# amelia_B_v1.net
KiCad netlist of a schematic drawn in EAGLE
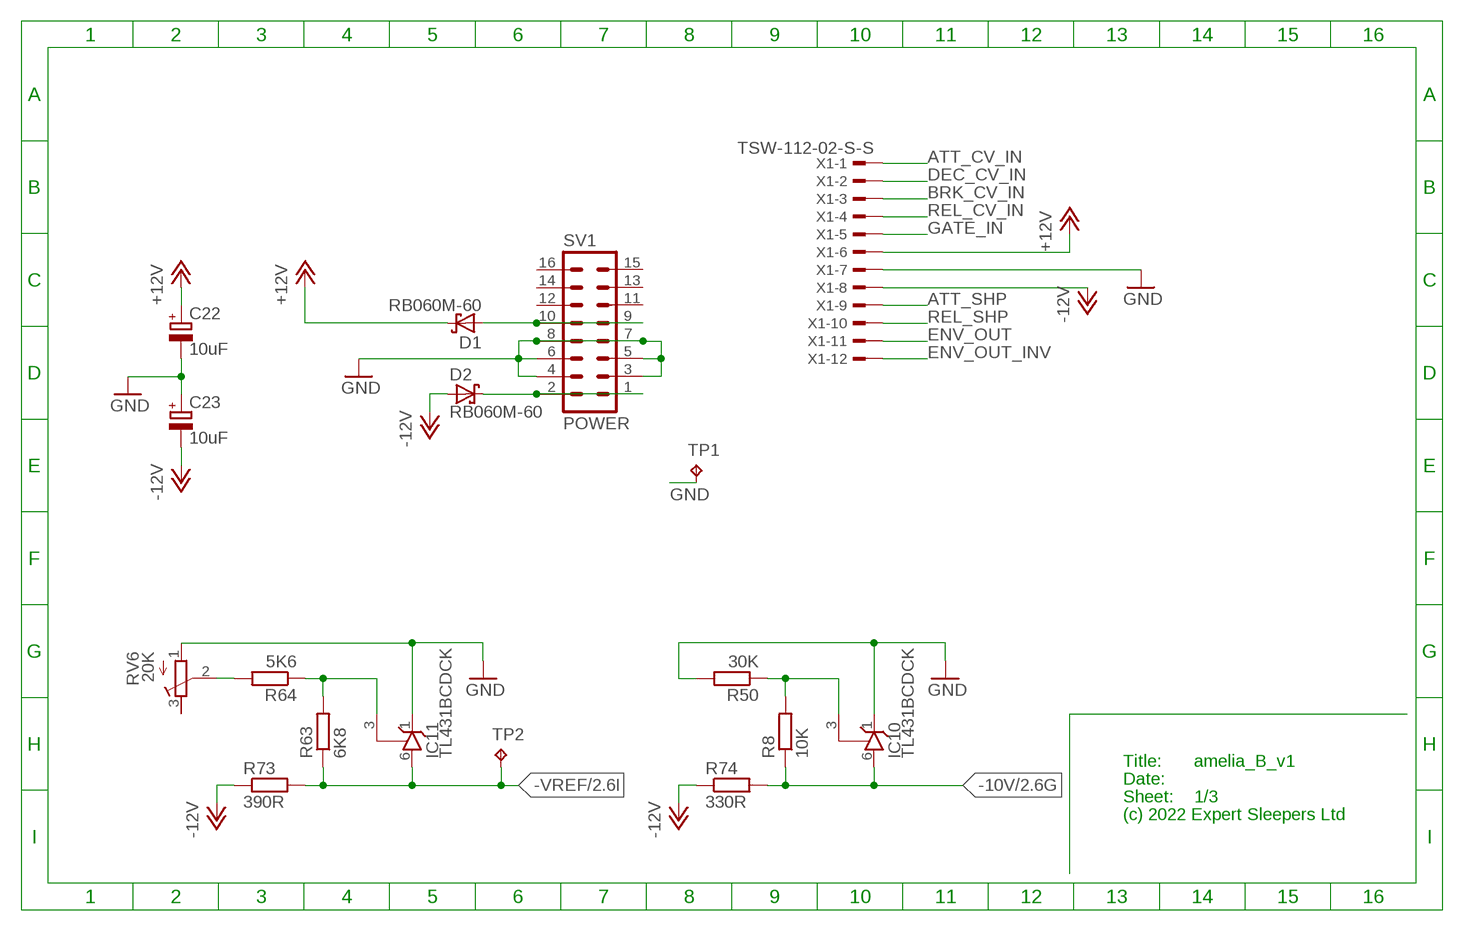
[diagram p0: schematic, sheet 1]
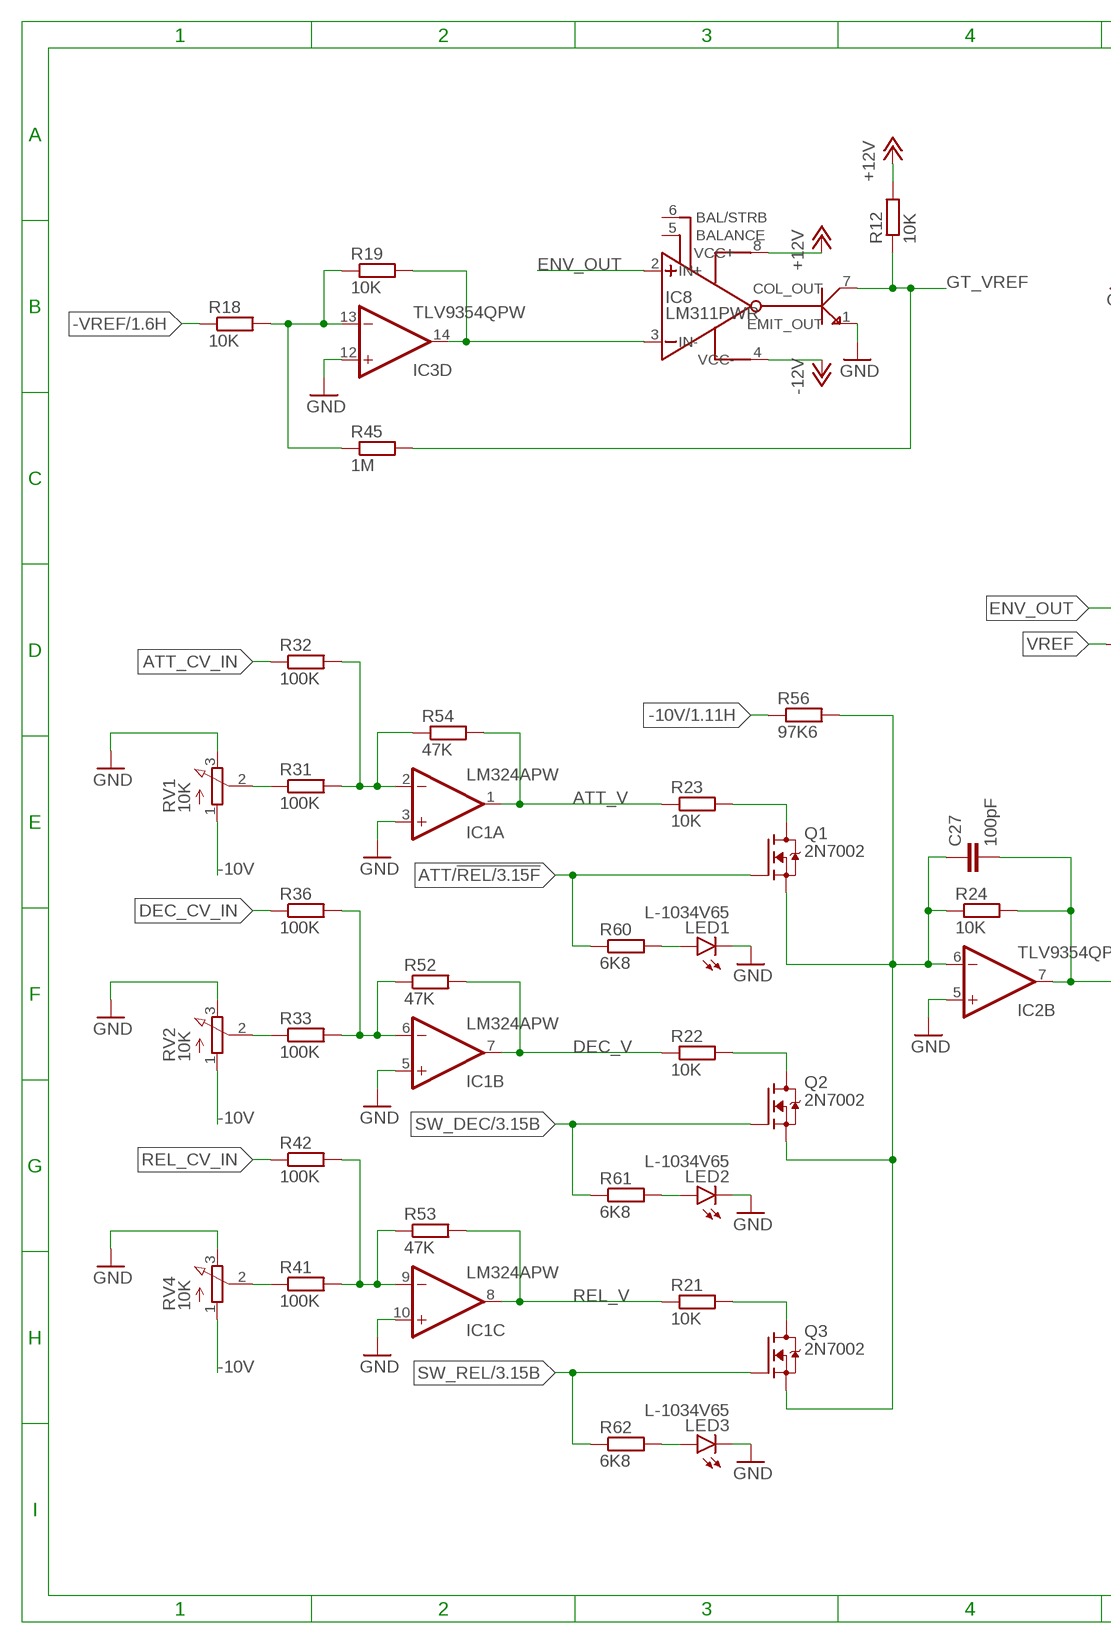
[diagram p1: schematic, sheet 2, part 1 of 2]
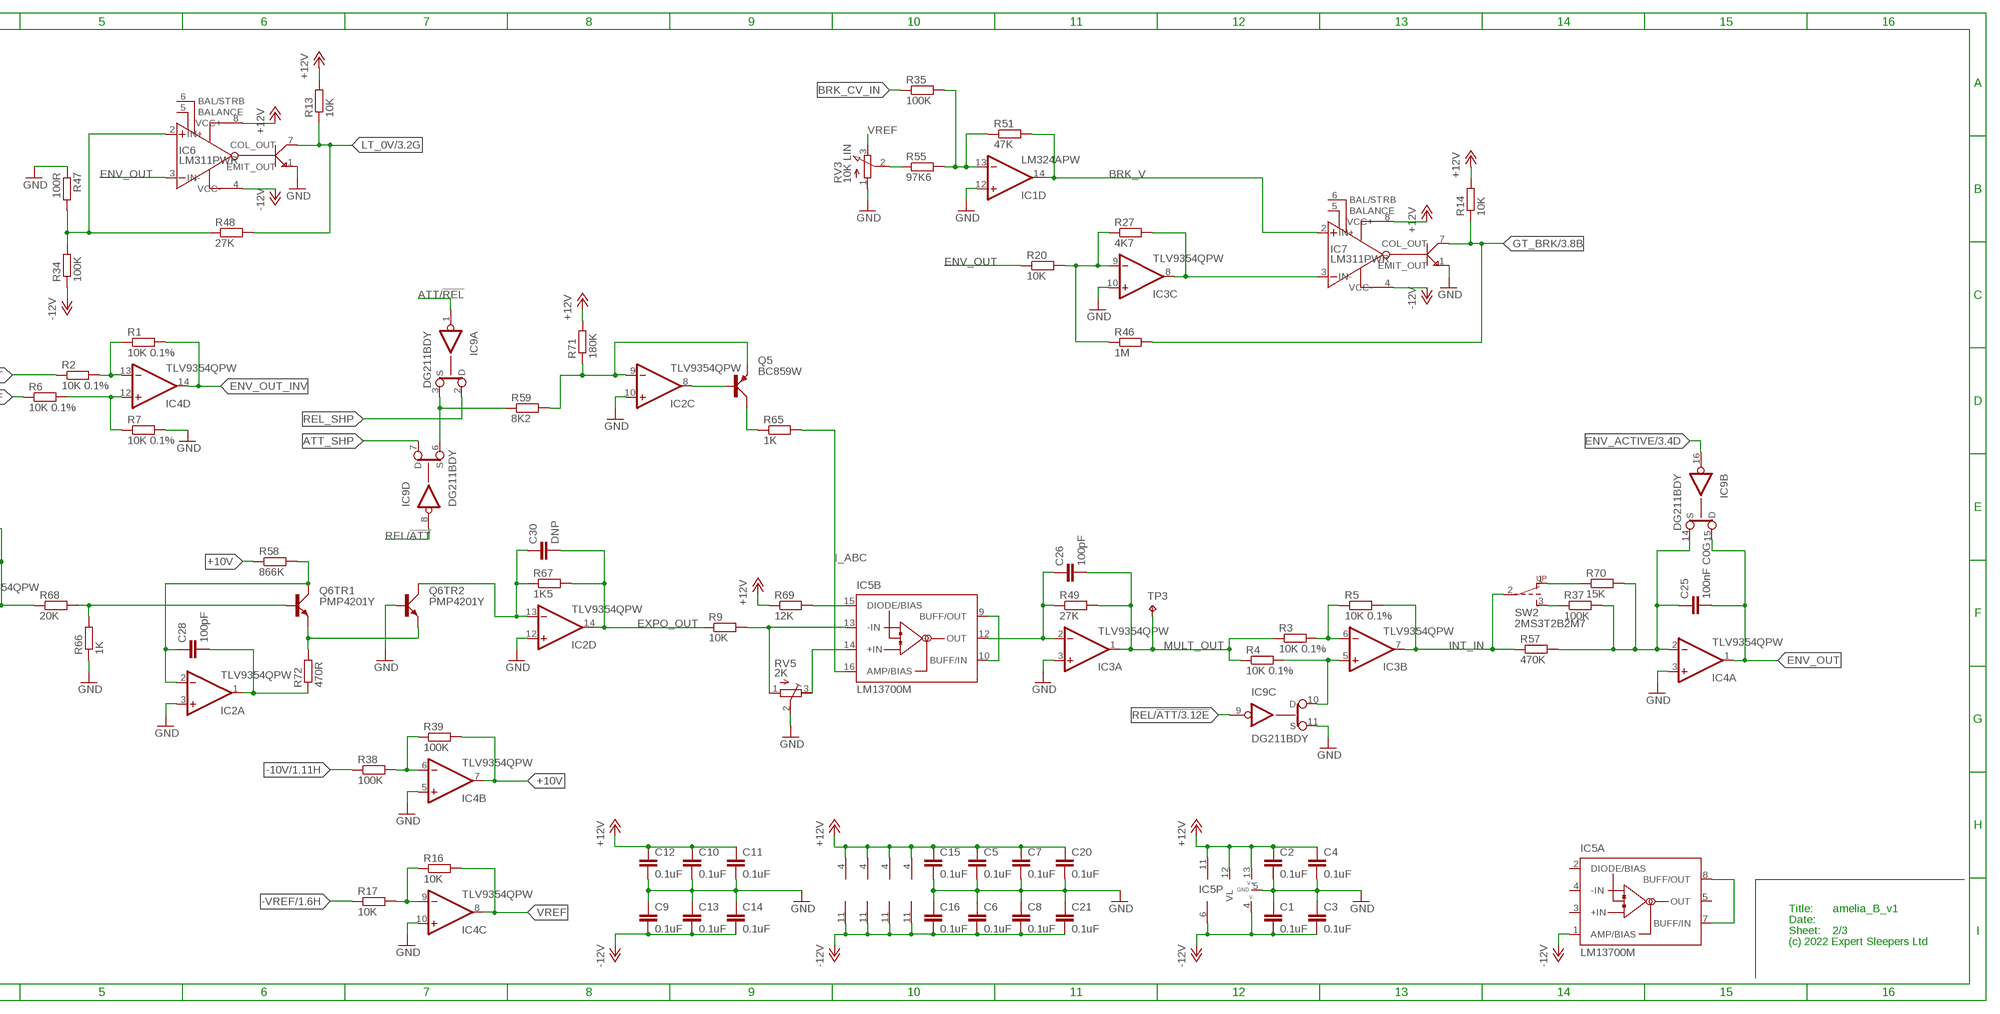
[diagram p2: schematic, sheet 2, part 2 of 2]
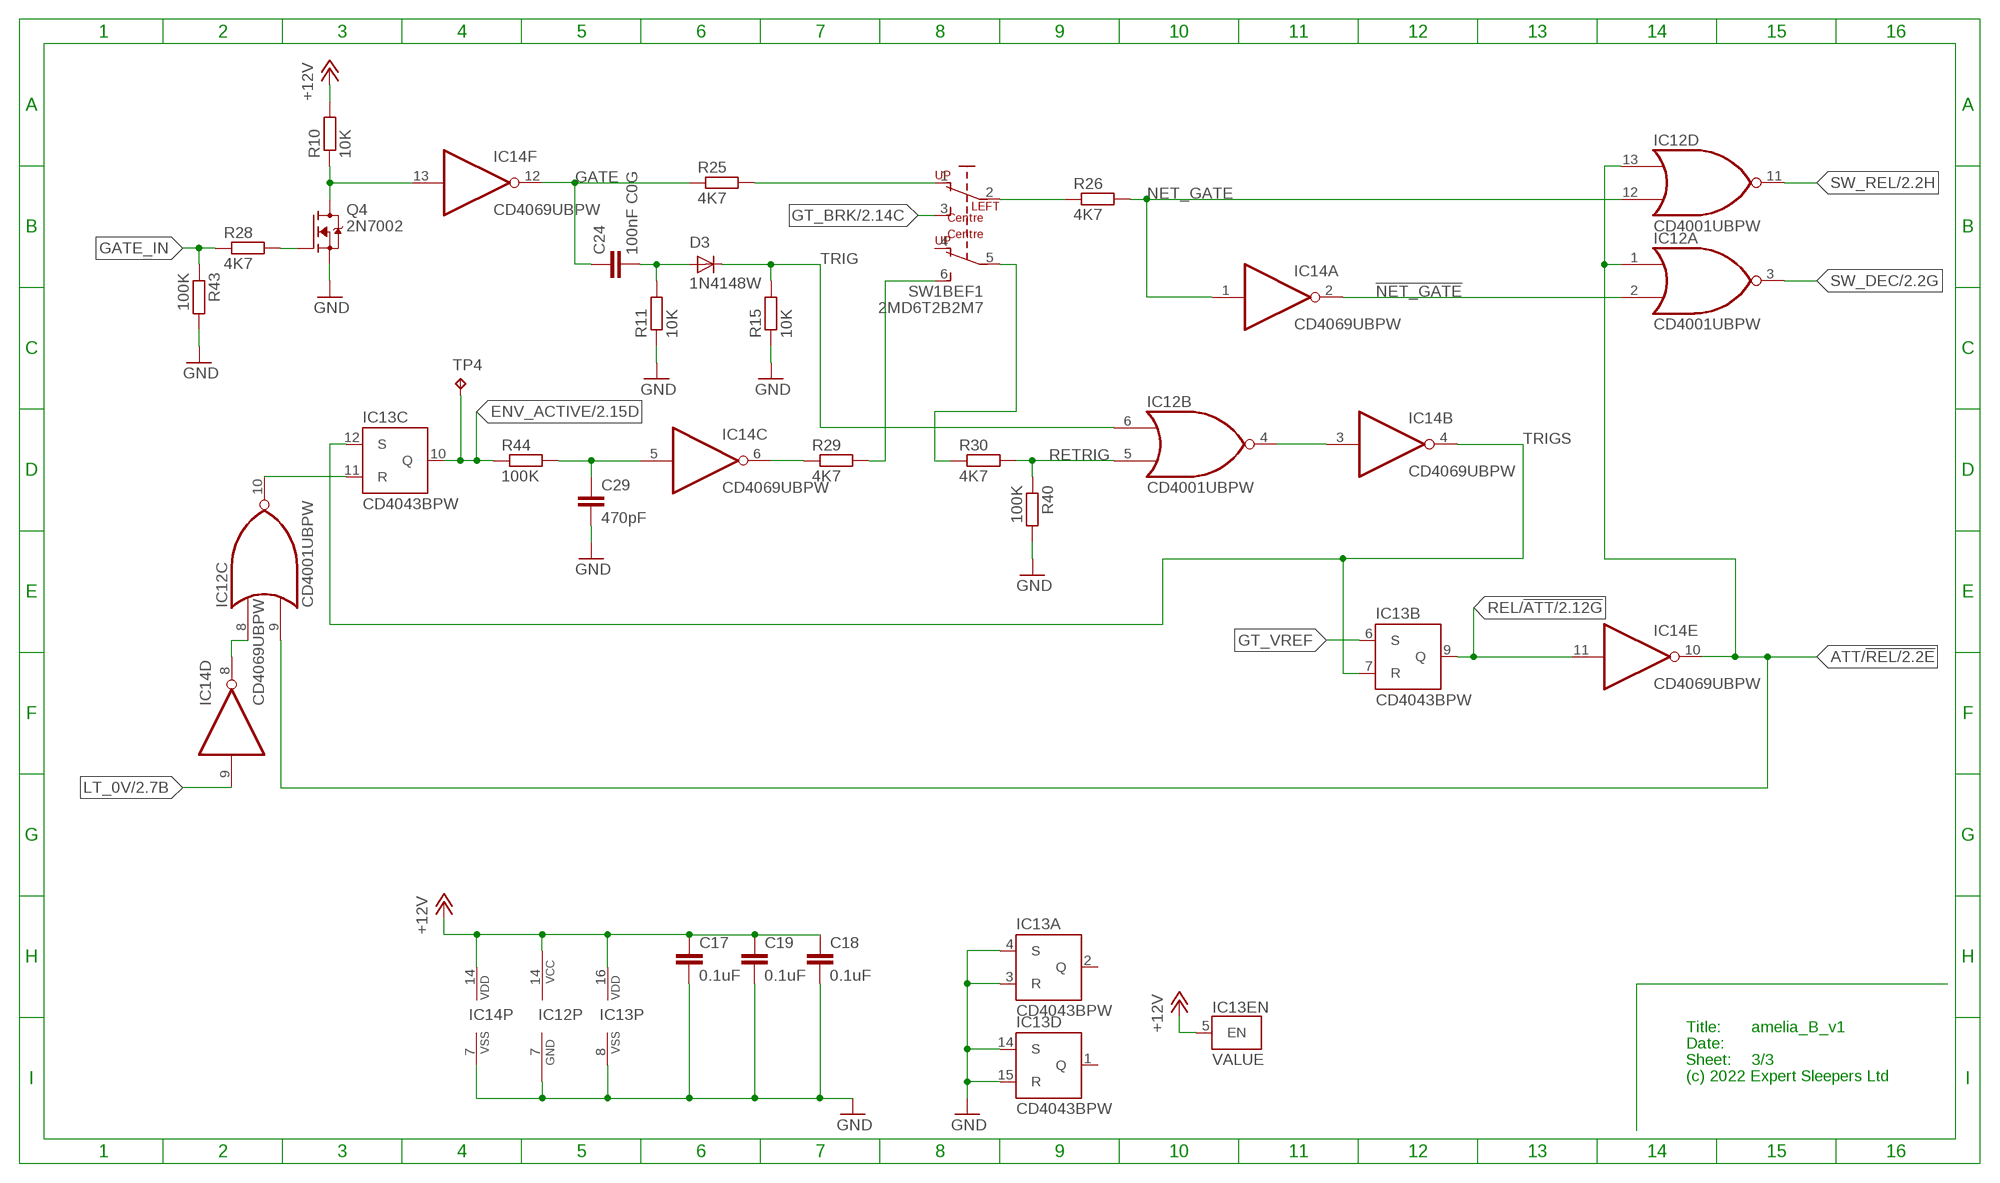
[diagram p3: schematic, sheet 3]

(export (version "E")
  (design (tool "Eeschema 10.0.6"))
  (components
    (comp (ref "C22")
      (value "10uF")
      (footprint "eagle-import:UD-4X5,8_NICHICON")
      (libsource (lib "eagle-import") (part "CPOL-EUUD-4X5,8"))
    )
    (comp (ref "C23")
      (value "10uF")
      (footprint "eagle-import:UD-4X5,8_NICHICON")
      (libsource (lib "eagle-import") (part "CPOL-EUUD-4X5,8"))
    )
    (comp (ref "D1")
      (value "RB060M-60")
      (footprint "eagle-import:SOD123FL")
      (libsource (lib "eagle-import") (part "RB060M-60"))
    )
    (comp (ref "D2")
      (value "RB060M-60")
      (footprint "eagle-import:SOD123FL")
      (libsource (lib "eagle-import") (part "RB060M-60"))
    )
    (comp (ref "IC10")
      (value "TL431BCDCK")
      (footprint "eagle-import:DCK_SC-70")
      (libsource (lib "eagle-import") (part "TL431DCKBC"))
    )
    (comp (ref "IC11")
      (value "TL431BCDCK")
      (footprint "eagle-import:DCK_SC-70")
      (libsource (lib "eagle-import") (part "TL431DCKBC"))
    )
    (comp (ref "R8")
      (value "10K")
      (footprint "eagle-import:R0603")
      (libsource (lib "eagle-import") (part "R-EU_R0603"))
    )
    (comp (ref "R50")
      (value "30K")
      (footprint "eagle-import:R0603")
      (libsource (lib "eagle-import") (part "R-EU_R0603"))
    )
    (comp (ref "R63")
      (value "6K8")
      (footprint "eagle-import:R0603")
      (libsource (lib "eagle-import") (part "R-EU_R0603"))
    )
    (comp (ref "R64")
      (value "5K6")
      (footprint "eagle-import:R0603")
      (libsource (lib "eagle-import") (part "R-EU_R0603"))
    )
    (comp (ref "R73")
      (value "390R")
      (footprint "eagle-import:R1206")
      (libsource (lib "eagle-import") (part "R-EU_R1206"))
    )
    (comp (ref "R74")
      (value "330R")
      (footprint "eagle-import:R1206")
      (libsource (lib "eagle-import") (part "R-EU_R1206"))
    )
    (comp (ref "RV6")
      (value "20K")
      (footprint "eagle-import:TC33X")
      (libsource (lib "eagle-import") (part "TC33X"))
    )
    (comp (ref "SV1")
      (value "POWER")
      (footprint "eagle-import:ML16")
      (libsource (lib "eagle-import") (part "ML16"))
    )
    (comp (ref "TP1")
      (value "RA2")
      (footprint "eagle-import:P1-13")
      (libsource (lib "eagle-import") (part "TPPAD1-13"))
    )
    (comp (ref "TP2")
      (value "RA2")
      (footprint "eagle-import:P1-13")
      (libsource (lib "eagle-import") (part "TPPAD1-13"))
    )
    (comp (ref "X1")
      (value "TSW-112-02-S-S")
      (footprint "eagle-import:TSW-112-02-S-S")
      (libsource (lib "eagle-import") (part "TSW-112-02-S-S"))
    )
    (comp (ref "C1")
      (value "0.1uF")
      (footprint "eagle-import:C0402")
      (libsource (lib "eagle-import") (part "C-EUC0402"))
    )
    (comp (ref "C2")
      (value "0.1uF")
      (footprint "eagle-import:C0402")
      (libsource (lib "eagle-import") (part "C-EUC0402"))
    )
    (comp (ref "C3")
      (value "0.1uF")
      (footprint "eagle-import:C0402")
      (libsource (lib "eagle-import") (part "C-EUC0402"))
    )
    (comp (ref "C4")
      (value "0.1uF")
      (footprint "eagle-import:C0402")
      (libsource (lib "eagle-import") (part "C-EUC0402"))
    )
    (comp (ref "C5")
      (value "0.1uF")
      (footprint "eagle-import:C0402")
      (libsource (lib "eagle-import") (part "C-EUC0402"))
    )
    (comp (ref "C6")
      (value "0.1uF")
      (footprint "eagle-import:C0402")
      (libsource (lib "eagle-import") (part "C-EUC0402"))
    )
    (comp (ref "C7")
      (value "0.1uF")
      (footprint "eagle-import:C0402")
      (libsource (lib "eagle-import") (part "C-EUC0402"))
    )
    (comp (ref "C8")
      (value "0.1uF")
      (footprint "eagle-import:C0402")
      (libsource (lib "eagle-import") (part "C-EUC0402"))
    )
    (comp (ref "C9")
      (value "0.1uF")
      (footprint "eagle-import:C0402")
      (libsource (lib "eagle-import") (part "C-EUC0402"))
    )
    (comp (ref "C10")
      (value "0.1uF")
      (footprint "eagle-import:C0402")
      (libsource (lib "eagle-import") (part "C-EUC0402"))
    )
    (comp (ref "C11")
      (value "0.1uF")
      (footprint "eagle-import:C0402")
      (libsource (lib "eagle-import") (part "C-EUC0402"))
    )
    (comp (ref "C12")
      (value "0.1uF")
      (footprint "eagle-import:C0402")
      (libsource (lib "eagle-import") (part "C-EUC0402"))
    )
    (comp (ref "C13")
      (value "0.1uF")
      (footprint "eagle-import:C0402")
      (libsource (lib "eagle-import") (part "C-EUC0402"))
    )
    (comp (ref "C14")
      (value "0.1uF")
      (footprint "eagle-import:C0402")
      (libsource (lib "eagle-import") (part "C-EUC0402"))
    )
    (comp (ref "C15")
      (value "0.1uF")
      (footprint "eagle-import:C0402")
      (libsource (lib "eagle-import") (part "C-EUC0402"))
    )
    (comp (ref "C16")
      (value "0.1uF")
      (footprint "eagle-import:C0402")
      (libsource (lib "eagle-import") (part "C-EUC0402"))
    )
    (comp (ref "C20")
      (value "0.1uF")
      (footprint "eagle-import:C0402")
      (libsource (lib "eagle-import") (part "C-EUC0402"))
    )
    (comp (ref "C21")
      (value "0.1uF")
      (footprint "eagle-import:C0402")
      (libsource (lib "eagle-import") (part "C-EUC0402"))
    )
    (comp (ref "C25")
      (value "100nF C0G")
      (footprint "eagle-import:C1206")
      (libsource (lib "eagle-import") (part "C-EUC1206"))
    )
    (comp (ref "C26")
      (value "100pF")
      (footprint "eagle-import:C0603")
      (libsource (lib "eagle-import") (part "C-EUC0603"))
    )
    (comp (ref "C27")
      (value "100pF")
      (footprint "eagle-import:C0603")
      (libsource (lib "eagle-import") (part "C-EUC0603"))
    )
    (comp (ref "C28")
      (value "100pF")
      (footprint "eagle-import:C0603")
      (libsource (lib "eagle-import") (part "C-EUC0603"))
    )
    (comp (ref "C30")
      (value "DNP")
      (footprint "eagle-import:C0603")
      (libsource (lib "eagle-import") (part "C-EUC0603"))
    )
    (comp (ref "IC1")
      (value "LM324APW")
      (footprint "eagle-import:PW_R-PDSO-G14")
      (libsource (lib "eagle-import") (part "TL074PW"))
    )
    (comp (ref "IC2")
      (value "TLV9354QPW")
      (footprint "eagle-import:PW_R-PDSO-G14")
      (libsource (lib "eagle-import") (part "TL074PW"))
    )
    (comp (ref "IC3")
      (value "TLV9354QPW")
      (footprint "eagle-import:PW_R-PDSO-G14")
      (libsource (lib "eagle-import") (part "TL074PW"))
    )
    (comp (ref "IC4")
      (value "TLV9354QPW")
      (footprint "eagle-import:PW_R-PDSO-G14")
      (libsource (lib "eagle-import") (part "TL074PW"))
    )
    (comp (ref "IC5")
      (value "LM13700M")
      (footprint "eagle-import:SO16")
      (libsource (lib "eagle-import") (part "LM13700M"))
    )
    (comp (ref "IC6")
      (value "LM311PWR")
      (footprint "eagle-import:SOP65P640X120-8N")
      (fields (field (name "MOUSER_PART_NUMBER") "595-LM311PWR"))
      (libsource (lib "eagle-import") (part "LM311PWR"))
    )
    (comp (ref "IC7")
      (value "LM311PWR")
      (footprint "eagle-import:SOP65P640X120-8N")
      (fields (field (name "MOUSER_PART_NUMBER") "595-LM311PWR"))
      (libsource (lib "eagle-import") (part "LM311PWR"))
    )
    (comp (ref "IC8")
      (value "LM311PWR")
      (footprint "eagle-import:SOP65P640X120-8N")
      (fields (field (name "MOUSER_PART_NUMBER") "595-LM311PWR"))
      (libsource (lib "eagle-import") (part "LM311PWR"))
    )
    (comp (ref "IC9")
      (value "DG211BDY")
      (footprint "eagle-import:SO16")
      (libsource (lib "eagle-import") (part "DG211CJD"))
    )
    (comp (ref "LED1")
      (value "L-1034V65")
      (footprint "eagle-import:L-1034_V6.5MM")
      (libsource (lib "eagle-import") (part "L-1034V65"))
    )
    (comp (ref "LED2")
      (value "L-1034V65")
      (footprint "eagle-import:L-1034_V6.5MM")
      (libsource (lib "eagle-import") (part "L-1034V65"))
    )
    (comp (ref "LED3")
      (value "L-1034V65")
      (footprint "eagle-import:L-1034_V6.5MM")
      (libsource (lib "eagle-import") (part "L-1034V65"))
    )
    (comp (ref "Q1")
      (value "2N7002")
      (footprint "eagle-import:SOT23")
      (libsource (lib "eagle-import") (part "2N7002"))
    )
    (comp (ref "Q2")
      (value "2N7002")
      (footprint "eagle-import:SOT23")
      (libsource (lib "eagle-import") (part "2N7002"))
    )
    (comp (ref "Q3")
      (value "2N7002")
      (footprint "eagle-import:SOT23")
      (libsource (lib "eagle-import") (part "2N7002"))
    )
    (comp (ref "Q5")
      (value "BC859W")
      (footprint "eagle-import:SOT323")
      (libsource (lib "eagle-import") (part "BC859W"))
    )
    (comp (ref "Q6")
      (value "PMP4201Y")
      (footprint "eagle-import:SOT65P210X110-6N")
      (fields
        (field (name "ARROW_PART_NUMBER") "PMP4201Y,135")
        (field (name "MOUSER_PART_NUMBER") "771-PMP4201Y135")
      )
      (libsource (lib "eagle-import") (part "PMP4201Y"))
    )
    (comp (ref "R1")
      (value "10K 0.1%")
      (footprint "eagle-import:R0603")
      (libsource (lib "eagle-import") (part "R-EU_R0603"))
    )
    (comp (ref "R2")
      (value "10K 0.1%")
      (footprint "eagle-import:R0603")
      (libsource (lib "eagle-import") (part "R-EU_R0603"))
    )
    (comp (ref "R3")
      (value "10K 0.1%")
      (footprint "eagle-import:R0603")
      (libsource (lib "eagle-import") (part "R-EU_R0603"))
    )
    (comp (ref "R4")
      (value "10K 0.1%")
      (footprint "eagle-import:R0603")
      (libsource (lib "eagle-import") (part "R-EU_R0603"))
    )
    (comp (ref "R5")
      (value "10K 0.1%")
      (footprint "eagle-import:R0603")
      (libsource (lib "eagle-import") (part "R-EU_R0603"))
    )
    (comp (ref "R6")
      (value "10K 0.1%")
      (footprint "eagle-import:R0603")
      (libsource (lib "eagle-import") (part "R-EU_R0603"))
    )
    (comp (ref "R7")
      (value "10K 0.1%")
      (footprint "eagle-import:R0603")
      (libsource (lib "eagle-import") (part "R-EU_R0603"))
    )
    (comp (ref "R9")
      (value "10K")
      (footprint "eagle-import:R0603")
      (libsource (lib "eagle-import") (part "R-EU_R0603"))
    )
    (comp (ref "R12")
      (value "10K")
      (footprint "eagle-import:R0603")
      (libsource (lib "eagle-import") (part "R-EU_R0603"))
    )
    (comp (ref "R13")
      (value "10K")
      (footprint "eagle-import:R0603")
      (libsource (lib "eagle-import") (part "R-EU_R0603"))
    )
    (comp (ref "R14")
      (value "10K")
      (footprint "eagle-import:R0603")
      (libsource (lib "eagle-import") (part "R-EU_R0603"))
    )
    (comp (ref "R16")
      (value "10K")
      (footprint "eagle-import:R0603")
      (libsource (lib "eagle-import") (part "R-EU_R0603"))
    )
    (comp (ref "R17")
      (value "10K")
      (footprint "eagle-import:R0603")
      (libsource (lib "eagle-import") (part "R-EU_R0603"))
    )
    (comp (ref "R18")
      (value "10K")
      (footprint "eagle-import:R0603")
      (libsource (lib "eagle-import") (part "R-EU_R0603"))
    )
    (comp (ref "R19")
      (value "10K")
      (footprint "eagle-import:R0603")
      (libsource (lib "eagle-import") (part "R-EU_R0603"))
    )
    (comp (ref "R20")
      (value "10K")
      (footprint "eagle-import:R0603")
      (libsource (lib "eagle-import") (part "R-EU_R0603"))
    )
    (comp (ref "R21")
      (value "10K")
      (footprint "eagle-import:R0603")
      (libsource (lib "eagle-import") (part "R-EU_R0603"))
    )
    (comp (ref "R22")
      (value "10K")
      (footprint "eagle-import:R0603")
      (libsource (lib "eagle-import") (part "R-EU_R0603"))
    )
    (comp (ref "R23")
      (value "10K")
      (footprint "eagle-import:R0603")
      (libsource (lib "eagle-import") (part "R-EU_R0603"))
    )
    (comp (ref "R24")
      (value "10K")
      (footprint "eagle-import:R0603")
      (libsource (lib "eagle-import") (part "R-EU_R0603"))
    )
    (comp (ref "R27")
      (value "4K7")
      (footprint "eagle-import:R0603")
      (libsource (lib "eagle-import") (part "R-EU_R0603"))
    )
    (comp (ref "R31")
      (value "100K")
      (footprint "eagle-import:R0603")
      (libsource (lib "eagle-import") (part "R-EU_R0603"))
    )
    (comp (ref "R32")
      (value "100K")
      (footprint "eagle-import:R0603")
      (libsource (lib "eagle-import") (part "R-EU_R0603"))
    )
    (comp (ref "R33")
      (value "100K")
      (footprint "eagle-import:R0603")
      (libsource (lib "eagle-import") (part "R-EU_R0603"))
    )
    (comp (ref "R34")
      (value "100K")
      (footprint "eagle-import:R0603")
      (libsource (lib "eagle-import") (part "R-EU_R0603"))
    )
    (comp (ref "R35")
      (value "100K")
      (footprint "eagle-import:R0603")
      (libsource (lib "eagle-import") (part "R-EU_R0603"))
    )
    (comp (ref "R36")
      (value "100K")
      (footprint "eagle-import:R0603")
      (libsource (lib "eagle-import") (part "R-EU_R0603"))
    )
    (comp (ref "R37")
      (value "100K")
      (footprint "eagle-import:R0603")
      (libsource (lib "eagle-import") (part "R-EU_R0603"))
    )
    (comp (ref "R38")
      (value "100K")
      (footprint "eagle-import:R0603")
      (libsource (lib "eagle-import") (part "R-EU_R0603"))
    )
    (comp (ref "R39")
      (value "100K")
      (footprint "eagle-import:R0603")
      (libsource (lib "eagle-import") (part "R-EU_R0603"))
    )
    (comp (ref "R41")
      (value "100K")
      (footprint "eagle-import:R0603")
      (libsource (lib "eagle-import") (part "R-EU_R0603"))
    )
    (comp (ref "R42")
      (value "100K")
      (footprint "eagle-import:R0603")
      (libsource (lib "eagle-import") (part "R-EU_R0603"))
    )
    (comp (ref "R45")
      (value "1M")
      (footprint "eagle-import:R0603")
      (libsource (lib "eagle-import") (part "R-EU_R0603"))
    )
    (comp (ref "R46")
      (value "1M")
      (footprint "eagle-import:R0603")
      (libsource (lib "eagle-import") (part "R-EU_R0603"))
    )
    (comp (ref "R47")
      (value "100R")
      (footprint "eagle-import:R0603")
      (libsource (lib "eagle-import") (part "R-EU_R0603"))
    )
    (comp (ref "R48")
      (value "27K")
      (footprint "eagle-import:R0603")
      (libsource (lib "eagle-import") (part "R-EU_R0603"))
    )
    (comp (ref "R49")
      (value "27K")
      (footprint "eagle-import:R0603")
      (libsource (lib "eagle-import") (part "R-EU_R0603"))
    )
    (comp (ref "R51")
      (value "47K")
      (footprint "eagle-import:R0603")
      (libsource (lib "eagle-import") (part "R-EU_R0603"))
    )
    (comp (ref "R52")
      (value "47K")
      (footprint "eagle-import:R0603")
      (libsource (lib "eagle-import") (part "R-EU_R0603"))
    )
    (comp (ref "R53")
      (value "47K")
      (footprint "eagle-import:R0603")
      (libsource (lib "eagle-import") (part "R-EU_R0603"))
    )
    (comp (ref "R54")
      (value "47K")
      (footprint "eagle-import:R0603")
      (libsource (lib "eagle-import") (part "R-EU_R0603"))
    )
    (comp (ref "R55")
      (value "97K6")
      (footprint "eagle-import:R0603")
      (libsource (lib "eagle-import") (part "R-EU_R0603"))
    )
    (comp (ref "R56")
      (value "97K6")
      (footprint "eagle-import:R0603")
      (libsource (lib "eagle-import") (part "R-EU_R0603"))
    )
    (comp (ref "R57")
      (value "470K")
      (footprint "eagle-import:R0603")
      (libsource (lib "eagle-import") (part "R-EU_R0603"))
    )
    (comp (ref "R58")
      (value "866K")
      (footprint "eagle-import:R0603")
      (libsource (lib "eagle-import") (part "R-EU_R0603"))
    )
    (comp (ref "R59")
      (value "8K2")
      (footprint "eagle-import:R0603")
      (libsource (lib "eagle-import") (part "R-EU_R0603"))
    )
    (comp (ref "R60")
      (value "6K8")
      (footprint "eagle-import:R0603")
      (libsource (lib "eagle-import") (part "R-EU_R0603"))
    )
    (comp (ref "R61")
      (value "6K8")
      (footprint "eagle-import:R0603")
      (libsource (lib "eagle-import") (part "R-EU_R0603"))
    )
    (comp (ref "R62")
      (value "6K8")
      (footprint "eagle-import:R0603")
      (libsource (lib "eagle-import") (part "R-EU_R0603"))
    )
    (comp (ref "R65")
      (value "1K")
      (footprint "eagle-import:R0603")
      (libsource (lib "eagle-import") (part "R-EU_R0603"))
    )
    (comp (ref "R66")
      (value "1K")
      (footprint "eagle-import:R0603")
      (libsource (lib "eagle-import") (part "R-EU_R0603"))
    )
    (comp (ref "R67")
      (value "1K5")
      (footprint "eagle-import:R0603")
      (libsource (lib "eagle-import") (part "R-EU_R0603"))
    )
    (comp (ref "R68")
      (value "20K")
      (footprint "eagle-import:R0603")
      (libsource (lib "eagle-import") (part "R-EU_R0603"))
    )
    (comp (ref "R69")
      (value "12K")
      (footprint "eagle-import:R0603")
      (libsource (lib "eagle-import") (part "R-EU_R0603"))
    )
    (comp (ref "R70")
      (value "15K")
      (footprint "eagle-import:R0603")
      (libsource (lib "eagle-import") (part "R-EU_R0603"))
    )
    (comp (ref "R71")
      (value "180K")
      (footprint "eagle-import:R0603")
      (libsource (lib "eagle-import") (part "R-EU_R0603"))
    )
    (comp (ref "R72")
      (value "470R")
      (footprint "eagle-import:R0603")
      (libsource (lib "eagle-import") (part "R-EU_R0603"))
    )
    (comp (ref "RV1")
      (value "10K")
      (footprint "eagle-import:RD1610NOA0X")
      (libsource (lib "eagle-import") (part "RD1610NOA0X"))
    )
    (comp (ref "RV2")
      (value "10K")
      (footprint "eagle-import:RD1610NOA0X")
      (libsource (lib "eagle-import") (part "RD1610NOA0X"))
    )
    (comp (ref "RV3")
      (value "10K LIN")
      (footprint "eagle-import:RD1610NOA0X")
      (libsource (lib "eagle-import") (part "RD1610NOA0X"))
    )
    (comp (ref "RV4")
      (value "10K")
      (footprint "eagle-import:RD1610NOA0X")
      (libsource (lib "eagle-import") (part "RD1610NOA0X"))
    )
    (comp (ref "RV5")
      (value "2K")
      (footprint "eagle-import:RTRIM3296W")
      (libsource (lib "eagle-import") (part "T93YA"))
    )
    (comp (ref "SW2")
      (value "2MS3T2B2M7")
      (footprint "eagle-import:2MS1T2B2M7RE")
      (libsource (lib "eagle-import") (part "2MS3M7T2B2"))
    )
    (comp (ref "TP3")
      (value "RA2")
      (footprint "eagle-import:P1-13")
      (libsource (lib "eagle-import") (part "TPPAD1-13"))
    )
    (comp (ref "C17")
      (value "0.1uF")
      (footprint "eagle-import:C0402")
      (libsource (lib "eagle-import") (part "C-EUC0402"))
    )
    (comp (ref "C18")
      (value "0.1uF")
      (footprint "eagle-import:C0402")
      (libsource (lib "eagle-import") (part "C-EUC0402"))
    )
    (comp (ref "C19")
      (value "0.1uF")
      (footprint "eagle-import:C0402")
      (libsource (lib "eagle-import") (part "C-EUC0402"))
    )
    (comp (ref "C24")
      (value "100nF C0G")
      (footprint "eagle-import:C1206")
      (libsource (lib "eagle-import") (part "C-EUC1206"))
    )
    (comp (ref "C29")
      (value "470pF")
      (footprint "eagle-import:C0603")
      (libsource (lib "eagle-import") (part "C-EUC0603"))
    )
    (comp (ref "D3")
      (value "1N4148W")
      (footprint "eagle-import:SOD123")
      (libsource (lib "eagle-import") (part "1N4148W"))
    )
    (comp (ref "IC12")
      (value "CD4001UBPW")
      (footprint "eagle-import:TSSOP14")
      (libsource (lib "eagle-import") (part "CD4001UBPW"))
    )
    (comp (ref "IC13")
      (value "CD4043BPW")
      (footprint "eagle-import:TSSOP16")
      (libsource (lib "eagle-import") (part "CD4043BPW"))
    )
    (comp (ref "IC14")
      (value "CD4069UBPW")
      (footprint "eagle-import:TSSOP14")
      (libsource (lib "eagle-import") (part "CD4069UBPW"))
    )
    (comp (ref "Q4")
      (value "2N7002")
      (footprint "eagle-import:SOT23")
      (libsource (lib "eagle-import") (part "2N7002"))
    )
    (comp (ref "R10")
      (value "10K")
      (footprint "eagle-import:R0603")
      (libsource (lib "eagle-import") (part "R-EU_R0603"))
    )
    (comp (ref "R11")
      (value "10K")
      (footprint "eagle-import:R0603")
      (libsource (lib "eagle-import") (part "R-EU_R0603"))
    )
    (comp (ref "R15")
      (value "10K")
      (footprint "eagle-import:R0603")
      (libsource (lib "eagle-import") (part "R-EU_R0603"))
    )
    (comp (ref "R25")
      (value "4K7")
      (footprint "eagle-import:R0603")
      (libsource (lib "eagle-import") (part "R-EU_R0603"))
    )
    (comp (ref "R26")
      (value "4K7")
      (footprint "eagle-import:R0603")
      (libsource (lib "eagle-import") (part "R-EU_R0603"))
    )
    (comp (ref "R28")
      (value "4K7")
      (footprint "eagle-import:R0603")
      (libsource (lib "eagle-import") (part "R-EU_R0603"))
    )
    (comp (ref "R29")
      (value "4K7")
      (footprint "eagle-import:R0603")
      (libsource (lib "eagle-import") (part "R-EU_R0603"))
    )
    (comp (ref "R30")
      (value "4K7")
      (footprint "eagle-import:R0603")
      (libsource (lib "eagle-import") (part "R-EU_R0603"))
    )
    (comp (ref "R40")
      (value "100K")
      (footprint "eagle-import:R0603")
      (libsource (lib "eagle-import") (part "R-EU_R0603"))
    )
    (comp (ref "R43")
      (value "100K")
      (footprint "eagle-import:R0603")
      (libsource (lib "eagle-import") (part "R-EU_R0603"))
    )
    (comp (ref "R44")
      (value "100K")
      (footprint "eagle-import:R0603")
      (libsource (lib "eagle-import") (part "R-EU_R0603"))
    )
    (comp (ref "SW1")
      (value "2MD6T2B2M7")
      (footprint "eagle-import:2MD1T2B2M7RE")
      (libsource (lib "eagle-import") (part "2MD6M7T2B2"))
    )
    (comp (ref "TP4")
      (value "RA2")
      (footprint "eagle-import:P1-13")
      (libsource (lib "eagle-import") (part "TPPAD1-13"))
    )
  )
  (nets
    (net (code "1") (name "+10V") (class "Default")
      (node (ref "IC4") (pin "7") (pinfunction "OUT_7") (pintype "output"))
      (node (ref "R39") (pin "2") (pinfunction "2_2") (pintype "passive"))
      (node (ref "R58") (pin "1") (pinfunction "1_1") (pintype "passive"))
    )
    (net (code "2") (name "+12V") (class "Default")
      (node (ref "C10") (pin "1") (pinfunction "1_1") (pintype "passive"))
      (node (ref "C11") (pin "1") (pinfunction "1_1") (pintype "passive"))
      (node (ref "C12") (pin "1") (pinfunction "1_1") (pintype "passive"))
      (node (ref "C15") (pin "1") (pinfunction "1_1") (pintype "passive"))
      (node (ref "C17") (pin "1") (pinfunction "1_1") (pintype "passive"))
      (node (ref "C18") (pin "1") (pinfunction "1_1") (pintype "passive"))
      (node (ref "C19") (pin "1") (pinfunction "1_1") (pintype "passive"))
      (node (ref "C2") (pin "1") (pinfunction "1_1") (pintype "passive"))
      (node (ref "C20") (pin "1") (pinfunction "1_1") (pintype "passive"))
      (node (ref "C22") (pin "+") (pinfunction "+_+") (pintype "passive"))
      (node (ref "C4") (pin "1") (pinfunction "1_1") (pintype "passive"))
      (node (ref "C5") (pin "1") (pinfunction "1_1") (pintype "passive"))
      (node (ref "C7") (pin "1") (pinfunction "1_1") (pintype "passive"))
      (node (ref "D1") (pin "C") (pinfunction "C_C") (pintype "passive"))
      (node (ref "IC1") (pin "4") (pinfunction "V+_4") (pintype "power_in"))
      (node (ref "IC12") (pin "14") (pinfunction "VCC_14") (pintype "power_in"))
      (node (ref "IC13") (pin "16") (pinfunction "VDD_16") (pintype "power_in"))
      (node (ref "IC13") (pin "5") (pinfunction "EN_5") (pintype "input"))
      (node (ref "IC14") (pin "14") (pinfunction "VDD_14") (pintype "power_in"))
      (node (ref "IC2") (pin "4") (pinfunction "V+_4") (pintype "power_in"))
      (node (ref "IC3") (pin "4") (pinfunction "V+_4") (pintype "power_in"))
      (node (ref "IC4") (pin "4") (pinfunction "V+_4") (pintype "power_in"))
      (node (ref "IC5") (pin "11") (pinfunction "V+_11") (pintype "power_in"))
      (node (ref "IC6") (pin "8") (pinfunction "VCC+_8") (pintype "power_in"))
      (node (ref "IC7") (pin "8") (pinfunction "VCC+_8") (pintype "power_in"))
      (node (ref "IC8") (pin "8") (pinfunction "VCC+_8") (pintype "power_in"))
      (node (ref "IC9") (pin "12") (pinfunction "VL_12") (pintype "input"))
      (node (ref "IC9") (pin "13") (pinfunction "V+_13") (pintype "power_in"))
      (node (ref "R10") (pin "2") (pinfunction "2_2") (pintype "passive"))
      (node (ref "R12") (pin "2") (pinfunction "2_2") (pintype "passive"))
      (node (ref "R13") (pin "2") (pinfunction "2_2") (pintype "passive"))
      (node (ref "R14") (pin "2") (pinfunction "2_2") (pintype "passive"))
      (node (ref "R69") (pin "1") (pinfunction "1_1") (pintype "passive"))
      (node (ref "R71") (pin "2") (pinfunction "2_2") (pintype "passive"))
      (node (ref "X1") (pin "6") (pinfunction "1_6") (pintype "passive"))
    )
    (net (code "3") (name "-10V") (class "Default")
      (node (ref "IC10") (pin "6") (pinfunction "A_6") (pintype "passive"))
      (node (ref "R38") (pin "1") (pinfunction "1_1") (pintype "passive"))
      (node (ref "R56") (pin "1") (pinfunction "1_1") (pintype "passive"))
      (node (ref "R74") (pin "2") (pinfunction "2_2") (pintype "passive"))
      (node (ref "R8") (pin "1") (pinfunction "1_1") (pintype "passive"))
      (node (ref "RV1") (pin "1") (pinfunction "A_1") (pintype "passive"))
      (node (ref "RV2") (pin "1") (pinfunction "A_1") (pintype "passive"))
      (node (ref "RV4") (pin "1") (pinfunction "A_1") (pintype "passive"))
    )
    (net (code "4") (name "-12V") (class "Default")
      (node (ref "C1") (pin "2") (pinfunction "2_2") (pintype "passive"))
      (node (ref "C13") (pin "2") (pinfunction "2_2") (pintype "passive"))
      (node (ref "C14") (pin "2") (pinfunction "2_2") (pintype "passive"))
      (node (ref "C16") (pin "2") (pinfunction "2_2") (pintype "passive"))
      (node (ref "C21") (pin "2") (pinfunction "2_2") (pintype "passive"))
      (node (ref "C23") (pin "-") (pinfunction "-_-") (pintype "passive"))
      (node (ref "C3") (pin "2") (pinfunction "2_2") (pintype "passive"))
      (node (ref "C6") (pin "2") (pinfunction "2_2") (pintype "passive"))
      (node (ref "C8") (pin "2") (pinfunction "2_2") (pintype "passive"))
      (node (ref "C9") (pin "2") (pinfunction "2_2") (pintype "passive"))
      (node (ref "D2") (pin "A") (pinfunction "A_A") (pintype "passive"))
      (node (ref "IC1") (pin "11") (pinfunction "V-_11") (pintype "power_in"))
      (node (ref "IC2") (pin "11") (pinfunction "V-_11") (pintype "power_in"))
      (node (ref "IC3") (pin "11") (pinfunction "V-_11") (pintype "power_in"))
      (node (ref "IC4") (pin "11") (pinfunction "V-_11") (pintype "power_in"))
      (node (ref "IC5") (pin "1") (pinfunction "AMP/BIAS_1") (pintype "passive"))
      (node (ref "IC5") (pin "6") (pinfunction "V-_6") (pintype "power_in"))
      (node (ref "IC6") (pin "4") (pinfunction "VCC-_4") (pintype "power_in"))
      (node (ref "IC7") (pin "4") (pinfunction "VCC-_4") (pintype "power_in"))
      (node (ref "IC8") (pin "4") (pinfunction "VCC-_4") (pintype "power_in"))
      (node (ref "IC9") (pin "4") (pinfunction "V-_4") (pintype "power_in"))
      (node (ref "R34") (pin "1") (pinfunction "1_1") (pintype "passive"))
      (node (ref "R73") (pin "1") (pinfunction "1_1") (pintype "passive"))
      (node (ref "R74") (pin "1") (pinfunction "1_1") (pintype "passive"))
      (node (ref "X1") (pin "8") (pinfunction "1_8") (pintype "passive"))
    )
    (net (code "5") (name "-VREF") (class "Default")
      (node (ref "IC11") (pin "6") (pinfunction "A_6") (pintype "passive"))
      (node (ref "R17") (pin "1") (pinfunction "1_1") (pintype "passive"))
      (node (ref "R18") (pin "1") (pinfunction "1_1") (pintype "passive"))
      (node (ref "R63") (pin "1") (pinfunction "1_1") (pintype "passive"))
      (node (ref "R73") (pin "2") (pinfunction "2_2") (pintype "passive"))
      (node (ref "TP2") (pin "TP") (pinfunction "TP_TP") (pintype "input"))
    )
    (net (code "6") (name "ATT_CV_IN") (class "Default")
      (node (ref "R32") (pin "1") (pinfunction "1_1") (pintype "passive"))
      (node (ref "X1") (pin "1") (pinfunction "1_1") (pintype "passive"))
    )
    (net (code "7") (name "ATT_SHP") (class "Default")
      (node (ref "IC9") (pin "7") (pinfunction "D_7") (pintype "bidirectional"))
      (node (ref "X1") (pin "9") (pinfunction "1_9") (pintype "passive"))
    )
    (net (code "8") (name "ATT_V") (class "Default")
      (node (ref "IC1") (pin "1") (pinfunction "OUT_1") (pintype "output"))
      (node (ref "R23") (pin "1") (pinfunction "1_1") (pintype "passive"))
      (node (ref "R54") (pin "2") (pinfunction "2_2") (pintype "passive"))
    )
    (net (code "9") (name "ATT{slash}~{REL}") (class "Default")
      (node (ref "IC12") (pin "1") (pinfunction "I0_1") (pintype "input"))
      (node (ref "IC12") (pin "13") (pinfunction "I0_13") (pintype "input"))
      (node (ref "IC12") (pin "9") (pinfunction "I1_9") (pintype "input"))
      (node (ref "IC14") (pin "10") (pinfunction "O_10") (pintype "output"))
      (node (ref "IC9") (pin "1") (pinfunction "IN_1") (pintype "input"))
      (node (ref "Q1") (pin "1") (pinfunction "G_1") (pintype "passive"))
      (node (ref "R60") (pin "1") (pinfunction "1_1") (pintype "passive"))
    )
    (net (code "10") (name "BRK_CV_IN") (class "Default")
      (node (ref "R35") (pin "1") (pinfunction "1_1") (pintype "passive"))
      (node (ref "X1") (pin "3") (pinfunction "1_3") (pintype "passive"))
    )
    (net (code "11") (name "BRK_V") (class "Default")
      (node (ref "IC1") (pin "14") (pinfunction "OUT_14") (pintype "output"))
      (node (ref "IC7") (pin "2") (pinfunction "IN+_2") (pintype "input"))
      (node (ref "R51") (pin "2") (pinfunction "2_2") (pintype "passive"))
    )
    (net (code "12") (name "DEC_CV_IN") (class "Default")
      (node (ref "R36") (pin "1") (pinfunction "1_1") (pintype "passive"))
      (node (ref "X1") (pin "2") (pinfunction "1_2") (pintype "passive"))
    )
    (net (code "13") (name "DEC_V") (class "Default")
      (node (ref "IC1") (pin "7") (pinfunction "OUT_7") (pintype "output"))
      (node (ref "R22") (pin "1") (pinfunction "1_1") (pintype "passive"))
      (node (ref "R52") (pin "2") (pinfunction "2_2") (pintype "passive"))
    )
    (net (code "14") (name "ENV_ACTIVE") (class "Default")
      (node (ref "IC13") (pin "10") (pinfunction "Q_10") (pintype "output"))
      (node (ref "IC9") (pin "16") (pinfunction "IN_16") (pintype "input"))
      (node (ref "R44") (pin "1") (pinfunction "1_1") (pintype "passive"))
      (node (ref "TP4") (pin "TP") (pinfunction "TP_TP") (pintype "input"))
    )
    (net (code "15") (name "ENV_OUT") (class "Default")
      (node (ref "C25") (pin "2") (pinfunction "2_2") (pintype "passive"))
      (node (ref "IC4") (pin "1") (pinfunction "OUT_1") (pintype "output"))
      (node (ref "IC6") (pin "3") (pinfunction "IN-_3") (pintype "input"))
      (node (ref "IC8") (pin "2") (pinfunction "IN+_2") (pintype "input"))
      (node (ref "IC9") (pin "15") (pinfunction "D_15") (pintype "bidirectional"))
      (node (ref "R2") (pin "1") (pinfunction "1_1") (pintype "passive"))
      (node (ref "R20") (pin "1") (pinfunction "1_1") (pintype "passive"))
      (node (ref "X1") (pin "11") (pinfunction "1_11") (pintype "passive"))
    )
    (net (code "16") (name "ENV_OUT_INV") (class "Default")
      (node (ref "IC4") (pin "14") (pinfunction "OUT_14") (pintype "output"))
      (node (ref "R1") (pin "2") (pinfunction "2_2") (pintype "passive"))
      (node (ref "X1") (pin "12") (pinfunction "1_12") (pintype "passive"))
    )
    (net (code "17") (name "EXPO_OUT") (class "Default")
      (node (ref "C30") (pin "2") (pinfunction "2_2") (pintype "passive"))
      (node (ref "IC2") (pin "14") (pinfunction "OUT_14") (pintype "output"))
      (node (ref "R67") (pin "2") (pinfunction "2_2") (pintype "passive"))
      (node (ref "R9") (pin "1") (pinfunction "1_1") (pintype "passive"))
    )
    (net (code "18") (name "GATE") (class "Default")
      (node (ref "C24") (pin "1") (pinfunction "1_1") (pintype "passive"))
      (node (ref "IC14") (pin "12") (pinfunction "O_12") (pintype "output"))
      (node (ref "R25") (pin "1") (pinfunction "1_1") (pintype "passive"))
    )
    (net (code "19") (name "GATE_IN") (class "Default")
      (node (ref "R28") (pin "1") (pinfunction "1_1") (pintype "passive"))
      (node (ref "R43") (pin "1") (pinfunction "1_1") (pintype "passive"))
      (node (ref "X1") (pin "5") (pinfunction "1_5") (pintype "passive"))
    )
    (net (code "20") (name "GND") (class "Default")
      (node (ref "C1") (pin "1") (pinfunction "1_1") (pintype "passive"))
      (node (ref "C10") (pin "2") (pinfunction "2_2") (pintype "passive"))
      (node (ref "C11") (pin "2") (pinfunction "2_2") (pintype "passive"))
      (node (ref "C12") (pin "2") (pinfunction "2_2") (pintype "passive"))
      (node (ref "C13") (pin "1") (pinfunction "1_1") (pintype "passive"))
      (node (ref "C14") (pin "1") (pinfunction "1_1") (pintype "passive"))
      (node (ref "C15") (pin "2") (pinfunction "2_2") (pintype "passive"))
      (node (ref "C16") (pin "1") (pinfunction "1_1") (pintype "passive"))
      (node (ref "C17") (pin "2") (pinfunction "2_2") (pintype "passive"))
      (node (ref "C18") (pin "2") (pinfunction "2_2") (pintype "passive"))
      (node (ref "C19") (pin "2") (pinfunction "2_2") (pintype "passive"))
      (node (ref "C2") (pin "2") (pinfunction "2_2") (pintype "passive"))
      (node (ref "C20") (pin "2") (pinfunction "2_2") (pintype "passive"))
      (node (ref "C21") (pin "1") (pinfunction "1_1") (pintype "passive"))
      (node (ref "C22") (pin "-") (pinfunction "-_-") (pintype "passive"))
      (node (ref "C23") (pin "+") (pinfunction "+_+") (pintype "passive"))
      (node (ref "C29") (pin "2") (pinfunction "2_2") (pintype "passive"))
      (node (ref "C3") (pin "1") (pinfunction "1_1") (pintype "passive"))
      (node (ref "C4") (pin "2") (pinfunction "2_2") (pintype "passive"))
      (node (ref "C5") (pin "2") (pinfunction "2_2") (pintype "passive"))
      (node (ref "C6") (pin "1") (pinfunction "1_1") (pintype "passive"))
      (node (ref "C7") (pin "2") (pinfunction "2_2") (pintype "passive"))
      (node (ref "C8") (pin "1") (pinfunction "1_1") (pintype "passive"))
      (node (ref "C9") (pin "1") (pinfunction "1_1") (pintype "passive"))
      (node (ref "IC1") (pin "10") (pinfunction "+IN_10") (pintype "input"))
      (node (ref "IC1") (pin "12") (pinfunction "+IN_12") (pintype "input"))
      (node (ref "IC1") (pin "3") (pinfunction "+IN_3") (pintype "input"))
      (node (ref "IC1") (pin "5") (pinfunction "+IN_5") (pintype "input"))
      (node (ref "IC10") (pin "1") (pinfunction "C_1") (pintype "passive"))
      (node (ref "IC11") (pin "1") (pinfunction "C_1") (pintype "passive"))
      (node (ref "IC12") (pin "7") (pinfunction "GND_7") (pintype "power_in"))
      (node (ref "IC13") (pin "14") (pinfunction "S_14") (pintype "input"))
      (node (ref "IC13") (pin "15") (pinfunction "R_15") (pintype "input"))
      (node (ref "IC13") (pin "3") (pinfunction "R_3") (pintype "input"))
      (node (ref "IC13") (pin "4") (pinfunction "S_4") (pintype "input"))
      (node (ref "IC13") (pin "8") (pinfunction "VSS_8") (pintype "power_in"))
      (node (ref "IC14") (pin "7") (pinfunction "VSS_7") (pintype "power_in"))
      (node (ref "IC2") (pin "10") (pinfunction "+IN_10") (pintype "input"))
      (node (ref "IC2") (pin "12") (pinfunction "+IN_12") (pintype "input"))
      (node (ref "IC2") (pin "3") (pinfunction "+IN_3") (pintype "input"))
      (node (ref "IC2") (pin "5") (pinfunction "+IN_5") (pintype "input"))
      (node (ref "IC3") (pin "10") (pinfunction "+IN_10") (pintype "input"))
      (node (ref "IC3") (pin "12") (pinfunction "+IN_12") (pintype "input"))
      (node (ref "IC3") (pin "3") (pinfunction "+IN_3") (pintype "input"))
      (node (ref "IC4") (pin "10") (pinfunction "+IN_10") (pintype "input"))
      (node (ref "IC4") (pin "3") (pinfunction "+IN_3") (pintype "input"))
      (node (ref "IC4") (pin "5") (pinfunction "+IN_5") (pintype "input"))
      (node (ref "IC6") (pin "1") (pinfunction "EMIT_OUT_1") (pintype "bidirectional"))
      (node (ref "IC7") (pin "1") (pinfunction "EMIT_OUT_1") (pintype "bidirectional"))
      (node (ref "IC8") (pin "1") (pinfunction "EMIT_OUT_1") (pintype "bidirectional"))
      (node (ref "IC9") (pin "11") (pinfunction "S_11") (pintype "bidirectional"))
      (node (ref "IC9") (pin "5") (pinfunction "GND_5") (pintype "power_in"))
      (node (ref "LED1") (pin "K") (pinfunction "C_K") (pintype "passive"))
      (node (ref "LED2") (pin "K") (pinfunction "C_K") (pintype "passive"))
      (node (ref "LED3") (pin "K") (pinfunction "C_K") (pintype "passive"))
      (node (ref "Q4") (pin "2") (pinfunction "S_2") (pintype "passive"))
      (node (ref "Q6") (pin "2") (pinfunction "B_2") (pintype "passive"))
      (node (ref "R11") (pin "1") (pinfunction "1_1") (pintype "passive"))
      (node (ref "R15") (pin "1") (pinfunction "1_1") (pintype "passive"))
      (node (ref "R40") (pin "2") (pinfunction "2_2") (pintype "passive"))
      (node (ref "R43") (pin "2") (pinfunction "2_2") (pintype "passive"))
      (node (ref "R47") (pin "1") (pinfunction "1_1") (pintype "passive"))
      (node (ref "R50") (pin "2") (pinfunction "2_2") (pintype "passive"))
      (node (ref "R66") (pin "1") (pinfunction "1_1") (pintype "passive"))
      (node (ref "R7") (pin "2") (pinfunction "2_2") (pintype "passive"))
      (node (ref "RV1") (pin "3") (pinfunction "E_3") (pintype "passive"))
      (node (ref "RV2") (pin "3") (pinfunction "E_3") (pintype "passive"))
      (node (ref "RV3") (pin "1") (pinfunction "A_1") (pintype "passive"))
      (node (ref "RV4") (pin "3") (pinfunction "E_3") (pintype "passive"))
      (node (ref "RV5") (pin "2") (pinfunction "S_2") (pintype "passive"))
      (node (ref "RV6") (pin "1") (pinfunction "A_1") (pintype "passive"))
      (node (ref "SV1") (pin "3") (pinfunction "3_3") (pintype "passive"))
      (node (ref "SV1") (pin "4") (pinfunction "4_4") (pintype "passive"))
      (node (ref "SV1") (pin "5") (pinfunction "5_5") (pintype "passive"))
      (node (ref "SV1") (pin "6") (pinfunction "6_6") (pintype "passive"))
      (node (ref "SV1") (pin "7") (pinfunction "7_7") (pintype "passive"))
      (node (ref "SV1") (pin "8") (pinfunction "8_8") (pintype "passive"))
      (node (ref "TP1") (pin "TP") (pinfunction "TP_TP") (pintype "input"))
      (node (ref "X1") (pin "7") (pinfunction "1_7") (pintype "passive"))
    )
    (net (code "21") (name "GT_BRK") (class "Default")
      (node (ref "IC7") (pin "7") (pinfunction "COL_OUT_7") (pintype "bidirectional"))
      (node (ref "R14") (pin "1") (pinfunction "1_1") (pintype "passive"))
      (node (ref "R46") (pin "2") (pinfunction "2_2") (pintype "passive"))
      (node (ref "SW1") (pin "3") (pinfunction "LD_3") (pintype "passive"))
    )
    (net (code "22") (name "GT_VREF") (class "Default")
      (node (ref "IC13") (pin "6") (pinfunction "S_6") (pintype "input"))
      (node (ref "IC8") (pin "7") (pinfunction "COL_OUT_7") (pintype "bidirectional"))
      (node (ref "R12") (pin "1") (pinfunction "1_1") (pintype "passive"))
      (node (ref "R45") (pin "2") (pinfunction "2_2") (pintype "passive"))
    )
    (net (code "23") (name "INT_IN") (class "Default")
      (node (ref "IC3") (pin "7") (pinfunction "OUT_7") (pintype "output"))
      (node (ref "R5") (pin "2") (pinfunction "2_2") (pintype "passive"))
      (node (ref "R57") (pin "1") (pinfunction "1_1") (pintype "passive"))
      (node (ref "SW2") (pin "2") (pinfunction "PR_2") (pintype "passive"))
    )
    (net (code "24") (name "I_ABC") (class "Default")
      (node (ref "IC5") (pin "16") (pinfunction "AMP/BIAS_16") (pintype "passive"))
      (node (ref "R65") (pin "2") (pinfunction "2_2") (pintype "passive"))
    )
    (net (code "25") (name "LT_0V") (class "Default")
      (node (ref "IC14") (pin "9") (pinfunction "I_9") (pintype "input"))
      (node (ref "IC6") (pin "7") (pinfunction "COL_OUT_7") (pintype "bidirectional"))
      (node (ref "R13") (pin "1") (pinfunction "1_1") (pintype "passive"))
      (node (ref "R48") (pin "2") (pinfunction "2_2") (pintype "passive"))
    )
    (net (code "26") (name "MULT_OUT") (class "Default")
      (node (ref "C26") (pin "2") (pinfunction "2_2") (pintype "passive"))
      (node (ref "IC3") (pin "1") (pinfunction "OUT_1") (pintype "output"))
      (node (ref "R3") (pin "1") (pinfunction "1_1") (pintype "passive"))
      (node (ref "R4") (pin "1") (pinfunction "1_1") (pintype "passive"))
      (node (ref "R49") (pin "2") (pinfunction "2_2") (pintype "passive"))
      (node (ref "TP3") (pin "TP") (pinfunction "TP_TP") (pintype "input"))
    )
    (net (code "27") (name "NET_GATE") (class "Default")
      (node (ref "IC12") (pin "12") (pinfunction "I1_12") (pintype "input"))
      (node (ref "IC14") (pin "1") (pinfunction "I_1") (pintype "input"))
      (node (ref "R26") (pin "2") (pinfunction "2_2") (pintype "passive"))
    )
    (net (code "28") (name "Net-(C24-Pad2)") (class "Default")
      (node (ref "C24") (pin "2") (pinfunction "2_2") (pintype "passive"))
      (node (ref "D3") (pin "A") (pinfunction "A_A") (pintype "passive"))
      (node (ref "R11") (pin "2") (pinfunction "2_2") (pintype "passive"))
    )
    (net (code "29") (name "Net-(D1-PadA)") (class "Default")
      (node (ref "D1") (pin "A") (pinfunction "A_A") (pintype "passive"))
      (node (ref "SV1") (pin "10") (pinfunction "10_10") (pintype "passive"))
      (node (ref "SV1") (pin "9") (pinfunction "9_9") (pintype "passive"))
    )
    (net (code "30") (name "Net-(D2-PadC)") (class "Default")
      (node (ref "D2") (pin "C") (pinfunction "C_C") (pintype "passive"))
      (node (ref "SV1") (pin "1") (pinfunction "1_1") (pintype "passive"))
      (node (ref "SV1") (pin "2") (pinfunction "2_2") (pintype "passive"))
    )
    (net (code "31") (name "Net-(IC1A--IN)") (class "Default")
      (node (ref "IC1") (pin "2") (pinfunction "-IN_2") (pintype "input"))
      (node (ref "R31") (pin "2") (pinfunction "2_2") (pintype "passive"))
      (node (ref "R32") (pin "2") (pinfunction "2_2") (pintype "passive"))
      (node (ref "R54") (pin "1") (pinfunction "1_1") (pintype "passive"))
    )
    (net (code "32") (name "Net-(IC1B--IN)") (class "Default")
      (node (ref "IC1") (pin "6") (pinfunction "-IN_6") (pintype "input"))
      (node (ref "R33") (pin "2") (pinfunction "2_2") (pintype "passive"))
      (node (ref "R36") (pin "2") (pinfunction "2_2") (pintype "passive"))
      (node (ref "R52") (pin "1") (pinfunction "1_1") (pintype "passive"))
    )
    (net (code "33") (name "Net-(IC1C--IN)") (class "Default")
      (node (ref "IC1") (pin "9") (pinfunction "-IN_9") (pintype "input"))
      (node (ref "R41") (pin "2") (pinfunction "2_2") (pintype "passive"))
      (node (ref "R42") (pin "2") (pinfunction "2_2") (pintype "passive"))
      (node (ref "R53") (pin "1") (pinfunction "1_1") (pintype "passive"))
    )
    (net (code "34") (name "Net-(IC1D--IN)") (class "Default")
      (node (ref "IC1") (pin "13") (pinfunction "-IN_13") (pintype "input"))
      (node (ref "R35") (pin "2") (pinfunction "2_2") (pintype "passive"))
      (node (ref "R51") (pin "1") (pinfunction "1_1") (pintype "passive"))
      (node (ref "R55") (pin "2") (pinfunction "2_2") (pintype "passive"))
    )
    (net (code "35") (name "Net-(IC2A--IN)") (class "Default")
      (node (ref "C28") (pin "1") (pinfunction "1_1") (pintype "passive"))
      (node (ref "IC2") (pin "2") (pinfunction "-IN_2") (pintype "input"))
      (node (ref "Q6") (pin "6") (pinfunction "C_6") (pintype "passive"))
      (node (ref "R58") (pin "2") (pinfunction "2_2") (pintype "passive"))
    )
    (net (code "36") (name "Net-(IC2A-OUT)") (class "Default")
      (node (ref "C28") (pin "2") (pinfunction "2_2") (pintype "passive"))
      (node (ref "IC2") (pin "1") (pinfunction "OUT_1") (pintype "output"))
      (node (ref "R72") (pin "1") (pinfunction "1_1") (pintype "passive"))
    )
    (net (code "37") (name "Net-(IC2B--IN)") (class "Default")
      (node (ref "C27") (pin "1") (pinfunction "1_1") (pintype "passive"))
      (node (ref "IC2") (pin "6") (pinfunction "-IN_6") (pintype "input"))
      (node (ref "Q1") (pin "2") (pinfunction "S_2") (pintype "passive"))
      (node (ref "Q2") (pin "2") (pinfunction "S_2") (pintype "passive"))
      (node (ref "Q3") (pin "2") (pinfunction "S_2") (pintype "passive"))
      (node (ref "R24") (pin "1") (pinfunction "1_1") (pintype "passive"))
      (node (ref "R56") (pin "2") (pinfunction "2_2") (pintype "passive"))
    )
    (net (code "38") (name "Net-(IC2B-OUT)") (class "Default")
      (node (ref "C27") (pin "2") (pinfunction "2_2") (pintype "passive"))
      (node (ref "IC2") (pin "7") (pinfunction "OUT_7") (pintype "output"))
      (node (ref "R24") (pin "2") (pinfunction "2_2") (pintype "passive"))
      (node (ref "R68") (pin "1") (pinfunction "1_1") (pintype "passive"))
    )
    (net (code "39") (name "Net-(IC2C--IN)") (class "Default")
      (node (ref "IC2") (pin "9") (pinfunction "-IN_9") (pintype "input"))
      (node (ref "Q5") (pin "2") (pinfunction "E_2") (pintype "passive"))
      (node (ref "R59") (pin "2") (pinfunction "2_2") (pintype "passive"))
      (node (ref "R71") (pin "1") (pinfunction "1_1") (pintype "passive"))
    )
    (net (code "40") (name "Net-(IC2C-OUT)") (class "Default")
      (node (ref "IC2") (pin "8") (pinfunction "OUT_8") (pintype "output"))
      (node (ref "Q5") (pin "1") (pinfunction "B_1") (pintype "passive"))
    )
    (net (code "41") (name "Net-(IC2D--IN)") (class "Default")
      (node (ref "C30") (pin "1") (pinfunction "1_1") (pintype "passive"))
      (node (ref "IC2") (pin "13") (pinfunction "-IN_13") (pintype "input"))
      (node (ref "Q6") (pin "3") (pinfunction "C_3") (pintype "passive"))
      (node (ref "R67") (pin "1") (pinfunction "1_1") (pintype "passive"))
    )
    (net (code "42") (name "Net-(IC3A--IN)") (class "Default")
      (node (ref "C26") (pin "1") (pinfunction "1_1") (pintype "passive"))
      (node (ref "IC3") (pin "2") (pinfunction "-IN_2") (pintype "input"))
      (node (ref "IC5") (pin "12") (pinfunction "OUT_12") (pintype "output"))
      (node (ref "R49") (pin "1") (pinfunction "1_1") (pintype "passive"))
    )
    (net (code "43") (name "Net-(IC3B-+IN)") (class "Default")
      (node (ref "IC3") (pin "5") (pinfunction "+IN_5") (pintype "input"))
      (node (ref "IC9") (pin "10") (pinfunction "D_10") (pintype "bidirectional"))
      (node (ref "R4") (pin "2") (pinfunction "2_2") (pintype "passive"))
    )
    (net (code "44") (name "Net-(IC3B--IN)") (class "Default")
      (node (ref "IC3") (pin "6") (pinfunction "-IN_6") (pintype "input"))
      (node (ref "R3") (pin "2") (pinfunction "2_2") (pintype "passive"))
      (node (ref "R5") (pin "1") (pinfunction "1_1") (pintype "passive"))
    )
    (net (code "45") (name "Net-(IC3C--IN)") (class "Default")
      (node (ref "IC3") (pin "9") (pinfunction "-IN_9") (pintype "input"))
      (node (ref "R20") (pin "2") (pinfunction "2_2") (pintype "passive"))
      (node (ref "R27") (pin "1") (pinfunction "1_1") (pintype "passive"))
      (node (ref "R46") (pin "1") (pinfunction "1_1") (pintype "passive"))
    )
    (net (code "46") (name "Net-(IC3C-OUT)") (class "Default")
      (node (ref "IC3") (pin "8") (pinfunction "OUT_8") (pintype "output"))
      (node (ref "IC7") (pin "3") (pinfunction "IN-_3") (pintype "input"))
      (node (ref "R27") (pin "2") (pinfunction "2_2") (pintype "passive"))
    )
    (net (code "47") (name "Net-(IC3D--IN)") (class "Default")
      (node (ref "IC3") (pin "13") (pinfunction "-IN_13") (pintype "input"))
      (node (ref "R18") (pin "2") (pinfunction "2_2") (pintype "passive"))
      (node (ref "R19") (pin "1") (pinfunction "1_1") (pintype "passive"))
      (node (ref "R45") (pin "1") (pinfunction "1_1") (pintype "passive"))
    )
    (net (code "48") (name "Net-(IC3D-OUT)") (class "Default")
      (node (ref "IC3") (pin "14") (pinfunction "OUT_14") (pintype "output"))
      (node (ref "IC8") (pin "3") (pinfunction "IN-_3") (pintype "input"))
      (node (ref "R19") (pin "2") (pinfunction "2_2") (pintype "passive"))
    )
    (net (code "49") (name "Net-(IC4A--IN)") (class "Default")
      (node (ref "C25") (pin "1") (pinfunction "1_1") (pintype "passive"))
      (node (ref "IC4") (pin "2") (pinfunction "-IN_2") (pintype "input"))
      (node (ref "IC9") (pin "14") (pinfunction "S_14") (pintype "bidirectional"))
      (node (ref "R37") (pin "2") (pinfunction "2_2") (pintype "passive"))
      (node (ref "R57") (pin "2") (pinfunction "2_2") (pintype "passive"))
      (node (ref "R70") (pin "2") (pinfunction "2_2") (pintype "passive"))
    )
    (net (code "50") (name "Net-(IC4B--IN)") (class "Default")
      (node (ref "IC4") (pin "6") (pinfunction "-IN_6") (pintype "input"))
      (node (ref "R38") (pin "2") (pinfunction "2_2") (pintype "passive"))
      (node (ref "R39") (pin "1") (pinfunction "1_1") (pintype "passive"))
    )
    (net (code "51") (name "Net-(IC4C--IN)") (class "Default")
      (node (ref "IC4") (pin "9") (pinfunction "-IN_9") (pintype "input"))
      (node (ref "R16") (pin "1") (pinfunction "1_1") (pintype "passive"))
      (node (ref "R17") (pin "2") (pinfunction "2_2") (pintype "passive"))
    )
    (net (code "52") (name "Net-(IC4D-+IN)") (class "Default")
      (node (ref "IC4") (pin "12") (pinfunction "+IN_12") (pintype "input"))
      (node (ref "R6") (pin "2") (pinfunction "2_2") (pintype "passive"))
      (node (ref "R7") (pin "1") (pinfunction "1_1") (pintype "passive"))
    )
    (net (code "53") (name "Net-(IC4D--IN)") (class "Default")
      (node (ref "IC4") (pin "13") (pinfunction "-IN_13") (pintype "input"))
      (node (ref "R1") (pin "1") (pinfunction "1_1") (pintype "passive"))
      (node (ref "R2") (pin "2") (pinfunction "2_2") (pintype "passive"))
    )
    (net (code "54") (name "Net-(IC5A-BUFF{slash}IN)") (class "Default")
      (node (ref "IC5") (pin "7") (pinfunction "BUFF/IN_7") (pintype "input"))
      (node (ref "IC5") (pin "8") (pinfunction "BUFF/OUT_8") (pintype "output"))
    )
    (net (code "55") (name "Net-(IC5B-+IN)") (class "Default")
      (node (ref "IC5") (pin "14") (pinfunction "+IN_14") (pintype "input"))
      (node (ref "RV5") (pin "3") (pinfunction "E_3") (pintype "passive"))
    )
    (net (code "56") (name "Net-(IC5B--IN)") (class "Default")
      (node (ref "IC5") (pin "13") (pinfunction "-IN_13") (pintype "input"))
      (node (ref "R9") (pin "2") (pinfunction "2_2") (pintype "passive"))
      (node (ref "RV5") (pin "1") (pinfunction "A_1") (pintype "passive"))
    )
    (net (code "57") (name "Net-(IC5B-BUFF{slash}IN)") (class "Default")
      (node (ref "IC5") (pin "10") (pinfunction "BUFF/IN_10") (pintype "input"))
      (node (ref "IC5") (pin "9") (pinfunction "BUFF/OUT_9") (pintype "output"))
    )
    (net (code "58") (name "Net-(IC5B-DIODE{slash}BIAS)") (class "Default")
      (node (ref "IC5") (pin "15") (pinfunction "DIODE/BIAS_15") (pintype "passive"))
      (node (ref "R69") (pin "2") (pinfunction "2_2") (pintype "passive"))
    )
    (net (code "59") (name "Net-(IC6-IN+)") (class "Default")
      (node (ref "IC6") (pin "2") (pinfunction "IN+_2") (pintype "input"))
      (node (ref "R34") (pin "2") (pinfunction "2_2") (pintype "passive"))
      (node (ref "R47") (pin "2") (pinfunction "2_2") (pintype "passive"))
      (node (ref "R48") (pin "1") (pinfunction "1_1") (pintype "passive"))
    )
    (net (code "60") (name "Net-(IC9A-S)") (class "Default")
      (node (ref "IC9") (pin "3") (pinfunction "S_3") (pintype "bidirectional"))
      (node (ref "IC9") (pin "6") (pinfunction "S_6") (pintype "bidirectional"))
      (node (ref "R59") (pin "1") (pinfunction "1_1") (pintype "passive"))
    )
    (net (code "61") (name "Net-(IC10-R)") (class "Default")
      (node (ref "IC10") (pin "3") (pinfunction "R_3") (pintype "passive"))
      (node (ref "R50") (pin "1") (pinfunction "1_1") (pintype "passive"))
      (node (ref "R8") (pin "2") (pinfunction "2_2") (pintype "passive"))
    )
    (net (code "62") (name "Net-(IC11-R)") (class "Default")
      (node (ref "IC11") (pin "3") (pinfunction "R_3") (pintype "passive"))
      (node (ref "R63") (pin "2") (pinfunction "2_2") (pintype "passive"))
      (node (ref "R64") (pin "1") (pinfunction "1_1") (pintype "passive"))
    )
    (net (code "63") (name "Net-(IC12B-O)") (class "Default")
      (node (ref "IC12") (pin "4") (pinfunction "O_4") (pintype "output"))
      (node (ref "IC14") (pin "3") (pinfunction "I_3") (pintype "input"))
    )
    (net (code "64") (name "Net-(IC12C-I0)") (class "Default")
      (node (ref "IC12") (pin "8") (pinfunction "I0_8") (pintype "input"))
      (node (ref "IC14") (pin "8") (pinfunction "O_8") (pintype "output"))
    )
    (net (code "65") (name "Net-(IC12C-O)") (class "Default")
      (node (ref "IC12") (pin "10") (pinfunction "O_10") (pintype "output"))
      (node (ref "IC13") (pin "11") (pinfunction "R_11") (pintype "input"))
    )
    (net (code "66") (name "Net-(IC14C-I)") (class "Default")
      (node (ref "C29") (pin "1") (pinfunction "1_1") (pintype "passive"))
      (node (ref "IC14") (pin "5") (pinfunction "I_5") (pintype "input"))
      (node (ref "R44") (pin "2") (pinfunction "2_2") (pintype "passive"))
    )
    (net (code "67") (name "Net-(IC14C-O)") (class "Default")
      (node (ref "IC14") (pin "6") (pinfunction "O_6") (pintype "output"))
      (node (ref "R29") (pin "1") (pinfunction "1_1") (pintype "passive"))
    )
    (net (code "68") (name "Net-(IC14F-I)") (class "Default")
      (node (ref "IC14") (pin "13") (pinfunction "I_13") (pintype "input"))
      (node (ref "Q4") (pin "3") (pinfunction "D_3") (pintype "passive"))
      (node (ref "R10") (pin "1") (pinfunction "1_1") (pintype "passive"))
    )
    (net (code "69") (name "Net-(LED1-PadA)") (class "Default")
      (node (ref "LED1") (pin "A") (pinfunction "A_A") (pintype "passive"))
      (node (ref "R60") (pin "2") (pinfunction "2_2") (pintype "passive"))
    )
    (net (code "70") (name "Net-(LED2-PadA)") (class "Default")
      (node (ref "LED2") (pin "A") (pinfunction "A_A") (pintype "passive"))
      (node (ref "R61") (pin "2") (pinfunction "2_2") (pintype "passive"))
    )
    (net (code "71") (name "Net-(LED3-PadA)") (class "Default")
      (node (ref "LED3") (pin "A") (pinfunction "A_A") (pintype "passive"))
      (node (ref "R62") (pin "2") (pinfunction "2_2") (pintype "passive"))
    )
    (net (code "72") (name "Net-(Q1-D)") (class "Default")
      (node (ref "Q1") (pin "3") (pinfunction "D_3") (pintype "passive"))
      (node (ref "R23") (pin "2") (pinfunction "2_2") (pintype "passive"))
    )
    (net (code "73") (name "Net-(Q2-D)") (class "Default")
      (node (ref "Q2") (pin "3") (pinfunction "D_3") (pintype "passive"))
      (node (ref "R22") (pin "2") (pinfunction "2_2") (pintype "passive"))
    )
    (net (code "74") (name "Net-(Q3-D)") (class "Default")
      (node (ref "Q3") (pin "3") (pinfunction "D_3") (pintype "passive"))
      (node (ref "R21") (pin "2") (pinfunction "2_2") (pintype "passive"))
    )
    (net (code "75") (name "Net-(Q4-G)") (class "Default")
      (node (ref "Q4") (pin "1") (pinfunction "G_1") (pintype "passive"))
      (node (ref "R28") (pin "2") (pinfunction "2_2") (pintype "passive"))
    )
    (net (code "76") (name "Net-(Q5-C)") (class "Default")
      (node (ref "Q5") (pin "3") (pinfunction "C_3") (pintype "passive"))
      (node (ref "R65") (pin "1") (pinfunction "1_1") (pintype "passive"))
    )
    (net (code "77") (name "Net-(Q6A-B)") (class "Default")
      (node (ref "Q6") (pin "1") (pinfunction "B_1") (pintype "passive"))
      (node (ref "R66") (pin "2") (pinfunction "2_2") (pintype "passive"))
      (node (ref "R68") (pin "2") (pinfunction "2_2") (pintype "passive"))
    )
    (net (code "78") (name "Net-(Q6A-E)") (class "Default")
      (node (ref "Q6") (pin "4") (pinfunction "E_4") (pintype "passive"))
      (node (ref "Q6") (pin "5") (pinfunction "E_5") (pintype "passive"))
      (node (ref "R72") (pin "2") (pinfunction "2_2") (pintype "passive"))
    )
    (net (code "79") (name "Net-(RV1-S)") (class "Default")
      (node (ref "R31") (pin "1") (pinfunction "1_1") (pintype "passive"))
      (node (ref "RV1") (pin "2") (pinfunction "S_2") (pintype "passive"))
    )
    (net (code "80") (name "Net-(RV2-S)") (class "Default")
      (node (ref "R33") (pin "1") (pinfunction "1_1") (pintype "passive"))
      (node (ref "RV2") (pin "2") (pinfunction "S_2") (pintype "passive"))
    )
    (net (code "81") (name "Net-(RV3-S)") (class "Default")
      (node (ref "R55") (pin "1") (pinfunction "1_1") (pintype "passive"))
      (node (ref "RV3") (pin "2") (pinfunction "S_2") (pintype "passive"))
    )
    (net (code "82") (name "Net-(RV4-S)") (class "Default")
      (node (ref "R41") (pin "1") (pinfunction "1_1") (pintype "passive"))
      (node (ref "RV4") (pin "2") (pinfunction "S_2") (pintype "passive"))
    )
    (net (code "83") (name "Net-(RV6-S)") (class "Default")
      (node (ref "R64") (pin "2") (pinfunction "2_2") (pintype "passive"))
      (node (ref "RV6") (pin "2") (pinfunction "S_2") (pintype "passive"))
    )
    (net (code "84") (name "Net-(SW1A-LU)") (class "Default")
      (node (ref "R25") (pin "2") (pinfunction "2_2") (pintype "passive"))
      (node (ref "SW1") (pin "1") (pinfunction "LU_1") (pintype "passive"))
    )
    (net (code "85") (name "Net-(SW1A-PL)") (class "Default")
      (node (ref "R26") (pin "1") (pinfunction "1_1") (pintype "passive"))
      (node (ref "SW1") (pin "2") (pinfunction "PL_2") (pintype "passive"))
    )
    (net (code "86") (name "Net-(SW1A-PR)") (class "Default")
      (node (ref "R30") (pin "1") (pinfunction "1_1") (pintype "passive"))
      (node (ref "SW1") (pin "5") (pinfunction "PR_5") (pintype "passive"))
    )
    (net (code "87") (name "Net-(SW1A-RD)") (class "Default")
      (node (ref "R29") (pin "2") (pinfunction "2_2") (pintype "passive"))
      (node (ref "SW1") (pin "6") (pinfunction "RD_6") (pintype "passive"))
    )
    (net (code "88") (name "Net-(SW2-RD)") (class "Default")
      (node (ref "R37") (pin "1") (pinfunction "1_1") (pintype "passive"))
      (node (ref "SW2") (pin "3") (pinfunction "RD_3") (pintype "passive"))
    )
    (net (code "89") (name "Net-(SW2-RU)") (class "Default")
      (node (ref "R70") (pin "1") (pinfunction "1_1") (pintype "passive"))
      (node (ref "SW2") (pin "1") (pinfunction "RU_1") (pintype "passive"))
    )
    (net (code "90") (name "REL_CV_IN") (class "Default")
      (node (ref "R42") (pin "1") (pinfunction "1_1") (pintype "passive"))
      (node (ref "X1") (pin "4") (pinfunction "1_4") (pintype "passive"))
    )
    (net (code "91") (name "REL_SHP") (class "Default")
      (node (ref "IC9") (pin "2") (pinfunction "D_2") (pintype "bidirectional"))
      (node (ref "X1") (pin "10") (pinfunction "1_10") (pintype "passive"))
    )
    (net (code "92") (name "REL_V") (class "Default")
      (node (ref "IC1") (pin "8") (pinfunction "OUT_8") (pintype "output"))
      (node (ref "R21") (pin "1") (pinfunction "1_1") (pintype "passive"))
      (node (ref "R53") (pin "2") (pinfunction "2_2") (pintype "passive"))
    )
    (net (code "93") (name "REL{slash}~{ATT}") (class "Default")
      (node (ref "IC13") (pin "9") (pinfunction "Q_9") (pintype "output"))
      (node (ref "IC14") (pin "11") (pinfunction "I_11") (pintype "input"))
      (node (ref "IC9") (pin "8") (pinfunction "IN_8") (pintype "input"))
      (node (ref "IC9") (pin "9") (pinfunction "IN_9") (pintype "input"))
    )
    (net (code "94") (name "RETRIG") (class "Default")
      (node (ref "IC12") (pin "5") (pinfunction "I1_5") (pintype "input"))
      (node (ref "R30") (pin "2") (pinfunction "2_2") (pintype "passive"))
      (node (ref "R40") (pin "1") (pinfunction "1_1") (pintype "passive"))
    )
    (net (code "95") (name "SW_DEC") (class "Default")
      (node (ref "IC12") (pin "3") (pinfunction "O_3") (pintype "output"))
      (node (ref "Q2") (pin "1") (pinfunction "G_1") (pintype "passive"))
      (node (ref "R61") (pin "1") (pinfunction "1_1") (pintype "passive"))
    )
    (net (code "96") (name "SW_REL") (class "Default")
      (node (ref "IC12") (pin "11") (pinfunction "O_11") (pintype "output"))
      (node (ref "Q3") (pin "1") (pinfunction "G_1") (pintype "passive"))
      (node (ref "R62") (pin "1") (pinfunction "1_1") (pintype "passive"))
    )
    (net (code "97") (name "TRIG") (class "Default")
      (node (ref "D3") (pin "C") (pinfunction "C_C") (pintype "passive"))
      (node (ref "IC12") (pin "6") (pinfunction "I0_6") (pintype "input"))
      (node (ref "R15") (pin "2") (pinfunction "2_2") (pintype "passive"))
    )
    (net (code "98") (name "TRIGS") (class "Default")
      (node (ref "IC13") (pin "12") (pinfunction "S_12") (pintype "input"))
      (node (ref "IC13") (pin "7") (pinfunction "R_7") (pintype "input"))
      (node (ref "IC14") (pin "4") (pinfunction "O_4") (pintype "output"))
    )
    (net (code "99") (name "VREF") (class "Default")
      (node (ref "IC4") (pin "8") (pinfunction "OUT_8") (pintype "output"))
      (node (ref "R16") (pin "2") (pinfunction "2_2") (pintype "passive"))
      (node (ref "R6") (pin "1") (pinfunction "1_1") (pintype "passive"))
      (node (ref "RV3") (pin "3") (pinfunction "E_3") (pintype "passive"))
    )
    (net (code "100") (name "unconnected-(IC5A-+IN-Pad3)") (class "Default")
      (node (ref "IC5") (pin "3") (pinfunction "+IN_3") (pintype "input"))
    )
    (net (code "101") (name "unconnected-(IC5A--IN-Pad4)") (class "Default")
      (node (ref "IC5") (pin "4") (pinfunction "-IN_4") (pintype "input"))
    )
    (net (code "102") (name "unconnected-(IC5A-DIODE{slash}BIAS-Pad2)") (class "Default")
      (node (ref "IC5") (pin "2") (pinfunction "DIODE/BIAS_2") (pintype "passive"))
    )
    (net (code "103") (name "unconnected-(IC5A-OUT-Pad5)") (class "Default")
      (node (ref "IC5") (pin "5") (pinfunction "OUT_5") (pintype "output"))
    )
    (net (code "104") (name "unconnected-(IC6-BALANCE-Pad5)") (class "Default")
      (node (ref "IC6") (pin "5") (pinfunction "BALANCE_5") (pintype "bidirectional"))
    )
    (net (code "105") (name "unconnected-(IC6-BAL{slash}STRB-Pad6)") (class "Default")
      (node (ref "IC6") (pin "6") (pinfunction "BAL/STRB_6") (pintype "bidirectional"))
    )
    (net (code "106") (name "unconnected-(IC7-BALANCE-Pad5)") (class "Default")
      (node (ref "IC7") (pin "5") (pinfunction "BALANCE_5") (pintype "bidirectional"))
    )
    (net (code "107") (name "unconnected-(IC7-BAL{slash}STRB-Pad6)") (class "Default")
      (node (ref "IC7") (pin "6") (pinfunction "BAL/STRB_6") (pintype "bidirectional"))
    )
    (net (code "108") (name "unconnected-(IC8-BALANCE-Pad5)") (class "Default")
      (node (ref "IC8") (pin "5") (pinfunction "BALANCE_5") (pintype "bidirectional"))
    )
    (net (code "109") (name "unconnected-(IC8-BAL{slash}STRB-Pad6)") (class "Default")
      (node (ref "IC8") (pin "6") (pinfunction "BAL/STRB_6") (pintype "bidirectional"))
    )
    (net (code "110") (name "unconnected-(IC13A-Q-Pad2)") (class "Default")
      (node (ref "IC13") (pin "2") (pinfunction "Q_2") (pintype "output"))
    )
    (net (code "111") (name "unconnected-(IC13D-Q-Pad1)") (class "Default")
      (node (ref "IC13") (pin "1") (pinfunction "Q_1") (pintype "output"))
    )
    (net (code "112") (name "unconnected-(RV6-E-Pad3)") (class "Default")
      (node (ref "RV6") (pin "3") (pinfunction "E_3") (pintype "passive"))
    )
    (net (code "113") (name "unconnected-(SV1-Pad11)") (class "Default")
      (node (ref "SV1") (pin "11") (pinfunction "11_11") (pintype "passive"))
    )
    (net (code "114") (name "unconnected-(SV1-Pad12)") (class "Default")
      (node (ref "SV1") (pin "12") (pinfunction "12_12") (pintype "passive"))
    )
    (net (code "115") (name "unconnected-(SV1-Pad13)") (class "Default")
      (node (ref "SV1") (pin "13") (pinfunction "13_13") (pintype "passive"))
    )
    (net (code "116") (name "unconnected-(SV1-Pad14)") (class "Default")
      (node (ref "SV1") (pin "14") (pinfunction "14_14") (pintype "passive"))
    )
    (net (code "117") (name "unconnected-(SV1-Pad15)") (class "Default")
      (node (ref "SV1") (pin "15") (pinfunction "15_15") (pintype "passive"))
    )
    (net (code "118") (name "unconnected-(SV1-Pad16)") (class "Default")
      (node (ref "SV1") (pin "16") (pinfunction "16_16") (pintype "passive"))
    )
    (net (code "119") (name "unconnected-(SW1A-RU-Pad4)") (class "Default")
      (node (ref "SW1") (pin "4") (pinfunction "RU_4") (pintype "passive"))
    )
    (net (code "120") (name "~{NET_GATE}") (class "Default")
      (node (ref "IC12") (pin "2") (pinfunction "I1_2") (pintype "input"))
      (node (ref "IC14") (pin "2") (pinfunction "O_2") (pintype "output"))
    )
  )
)
